# ETH-PHY.net
KiCad netlist of a schematic drawn in Altium Designer
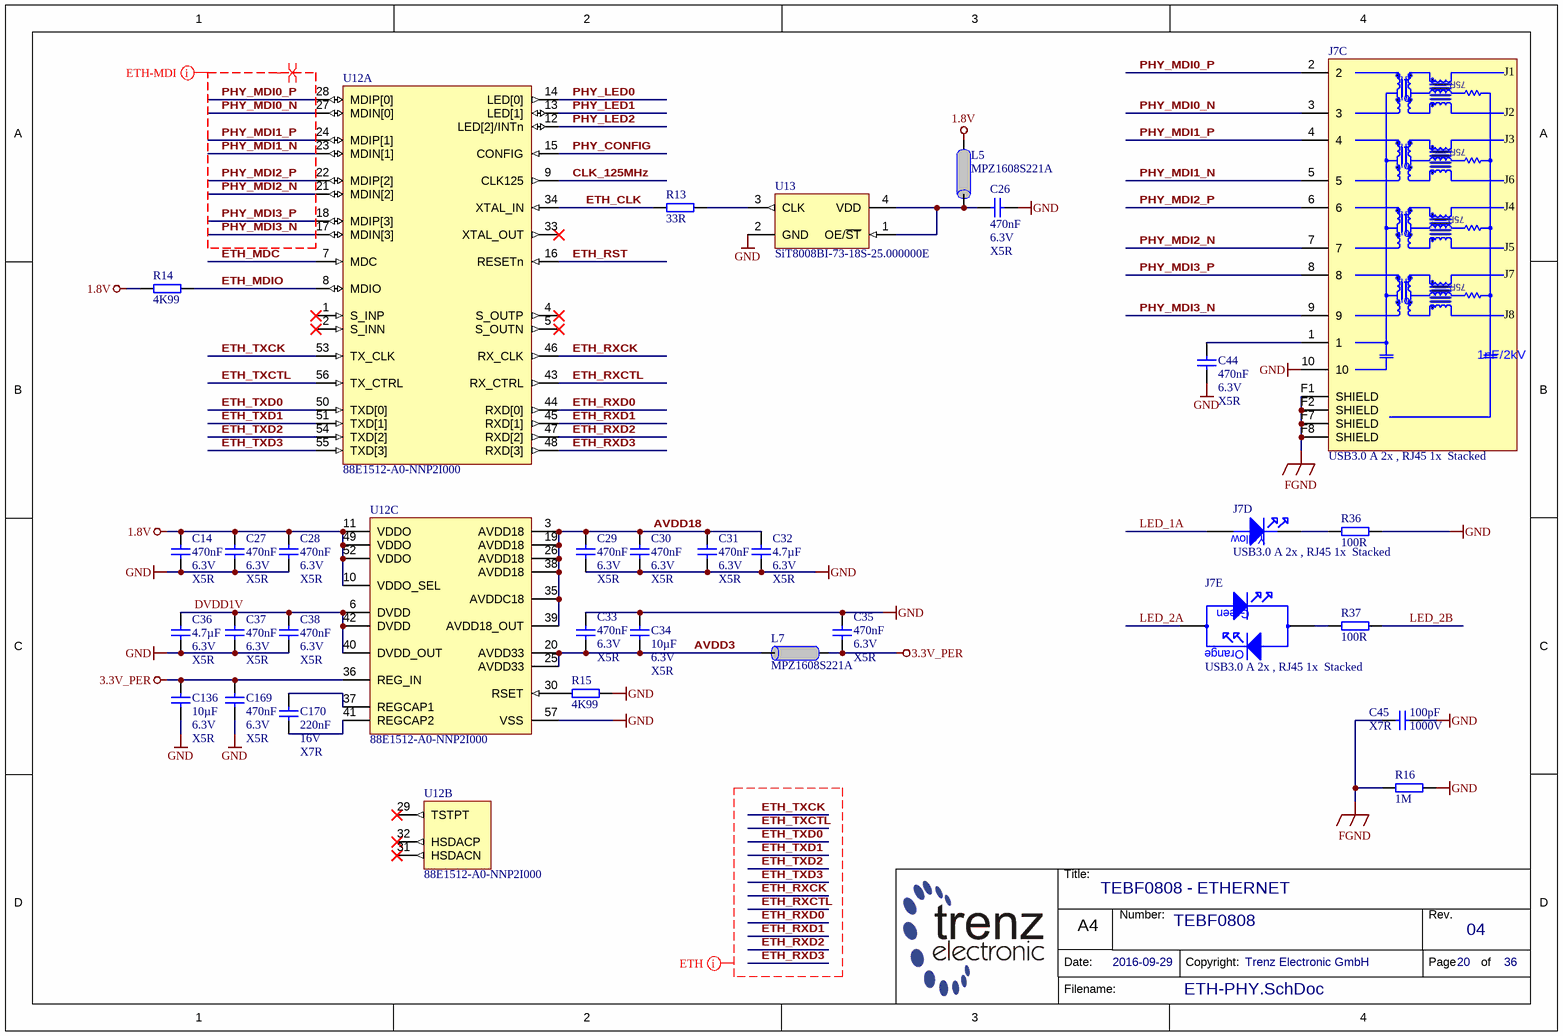
[diagram p0: ETH-PHY.SchDoc]

(export (version "E")
  (design (tool "Eeschema 10.0.6"))
  (components
    (comp (ref "C14")
      (value "470nF")
      (footprint "CAPC1005X55N")
      (description "KON 470nF 6,3V X5R SMD")
      (fields (field (name "VOLTAGE") "6.3V") (field (name "TECHNOLOGY") "X5R"))
      (libsource (lib "TE") (part "CAP-NP"))
    )
    (comp (ref "C26")
      (value "470nF")
      (footprint "CAPC1005X55N")
      (description "KON 470nF 6,3V X5R SMD")
      (fields (field (name "VOLTAGE") "6.3V") (field (name "TECHNOLOGY") "X5R"))
      (libsource (lib "TE") (part "CAP-NP"))
    )
    (comp (ref "C27")
      (value "470nF")
      (footprint "CAPC1005X55N")
      (description "KON 470nF 6,3V X5R SMD")
      (fields (field (name "VOLTAGE") "6.3V") (field (name "TECHNOLOGY") "X5R"))
      (libsource (lib "TE") (part "CAP-NP"))
    )
    (comp (ref "C28")
      (value "470nF")
      (footprint "CAPC1005X55N")
      (description "KON 470nF 6,3V X5R SMD")
      (fields (field (name "VOLTAGE") "6.3V") (field (name "TECHNOLOGY") "X5R"))
      (libsource (lib "TE") (part "CAP-NP"))
    )
    (comp (ref "C29")
      (value "470nF")
      (footprint "CAPC1005X55N")
      (description "KON 470nF 6,3V X5R SMD")
      (fields (field (name "VOLTAGE") "6.3V") (field (name "TECHNOLOGY") "X5R"))
      (libsource (lib "TE") (part "CAP-NP"))
    )
    (comp (ref "C30")
      (value "470nF")
      (footprint "CAPC1005X55N")
      (description "KON 470nF 6,3V X5R SMD")
      (fields (field (name "VOLTAGE") "6.3V") (field (name "TECHNOLOGY") "X5R"))
      (libsource (lib "TE") (part "CAP-NP"))
    )
    (comp (ref "C31")
      (value "470nF")
      (footprint "CAPC1005X55N")
      (description "KON 470nF 6,3V X5R SMD")
      (fields (field (name "VOLTAGE") "6.3V") (field (name "TECHNOLOGY") "X5R"))
      (libsource (lib "TE") (part "CAP-NP"))
    )
    (comp (ref "C32")
      (value "4.7µF")
      (footprint "CAPC1005X60N")
      (description "KON 4.7µF 6.3V X5R SMD 20%")
      (fields
        (field (name "VOLTAGE") "6.3V")
        (field (name "TECHNOLOGY") "X5R")
        (field (name "TOLERANCE") "20%")
      )
      (libsource (lib "TE") (part "CAP-NP"))
    )
    (comp (ref "C33")
      (value "470nF")
      (footprint "CAPC1005X55N")
      (description "KON 470nF 6,3V X5R SMD")
      (fields (field (name "VOLTAGE") "6.3V") (field (name "TECHNOLOGY") "X5R"))
      (libsource (lib "TE") (part "CAP-NP"))
    )
    (comp (ref "C34")
      (value "10µF")
      (footprint "CAPC1608X90N")
      (description "KON 10µF 6,3V X5R SMD")
      (fields (field (name "VOLTAGE") "6.3V") (field (name "TECHNOLOGY") "X5R"))
      (libsource (lib "TE") (part "CAP-NP"))
    )
    (comp (ref "C35")
      (value "470nF")
      (footprint "CAPC1005X55N")
      (description "KON 470nF 6,3V X5R SMD")
      (fields (field (name "VOLTAGE") "6.3V") (field (name "TECHNOLOGY") "X5R"))
      (libsource (lib "TE") (part "CAP-NP"))
    )
    (comp (ref "C36")
      (value "4.7µF")
      (footprint "CAPC1005X60N")
      (description "KON 4.7µF 6.3V X5R SMD 20%")
      (fields
        (field (name "VOLTAGE") "6.3V")
        (field (name "TECHNOLOGY") "X5R")
        (field (name "TOLERANCE") "20%")
      )
      (libsource (lib "TE") (part "CAP-NP"))
    )
    (comp (ref "C37")
      (value "470nF")
      (footprint "CAPC1005X55N")
      (description "KON 470nF 6,3V X5R SMD")
      (fields (field (name "VOLTAGE") "6.3V") (field (name "TECHNOLOGY") "X5R"))
      (libsource (lib "TE") (part "CAP-NP"))
    )
    (comp (ref "C38")
      (value "470nF")
      (footprint "CAPC1005X55N")
      (description "KON 470nF 6,3V X5R SMD")
      (fields (field (name "VOLTAGE") "6.3V") (field (name "TECHNOLOGY") "X5R"))
      (libsource (lib "TE") (part "CAP-NP"))
    )
    (comp (ref "C44")
      (value "470nF")
      (footprint "CAPC1005X55N")
      (description "KON 470nF 6,3V X5R SMD")
      (fields (field (name "VOLTAGE") "6.3V") (field (name "TECHNOLOGY") "X5R"))
      (libsource (lib "TE") (part "CAP-NP"))
    )
    (comp (ref "C45")
      (value "100pF")
      (footprint "CAPC3216X180N")
      (description "KON 100pF 1000V X7R 10%")
      (fields
        (field (name "VOLTAGE") "X7R")
        (field (name "TECHNOLOGY") "1000V")
        (field (name "TOLERANCE") "10%")
      )
      (libsource (lib "TE") (part "CAP-NP"))
    )
    (comp (ref "C136")
      (value "10µF")
      (footprint "CAPC1608X90N")
      (description "KON 10µF 6,3V X5R SMD")
      (fields (field (name "VOLTAGE") "6.3V") (field (name "TECHNOLOGY") "X5R"))
      (libsource (lib "TE") (part "CAP-NP"))
    )
    (comp (ref "C169")
      (value "470nF")
      (footprint "CAPC1005X55N")
      (description "KON 470nF 6,3V X5R SMD")
      (fields (field (name "VOLTAGE") "6.3V") (field (name "TECHNOLOGY") "X5R"))
      (libsource (lib "TE") (part "CAP-NP"))
    )
    (comp (ref "C170")
      (value "220nF")
      (footprint "CAPC1005X55N")
      (description "KON 220nF 16V X7R SMD")
      (fields (field (name "VOLTAGE") "16V") (field (name "TECHNOLOGY") "X7R"))
      (libsource (lib "TE") (part "CAP-NP"))
    )
    (comp (ref "J7")
      (value "USB3.0 A 2x , RJ45 1x  Stacked")
      (footprint "7497110616")
      (libsource (lib "") (part "7497110616_1"))
    )
    (comp (ref "L5")
      (value "MPZ1608S221A")
      (footprint "INDC1608X95N")
      (description "Ferritdurchführung MPZ1608S221A")
      (libsource (lib "TE") (part "Ferritperle"))
    )
    (comp (ref "L7")
      (value "MPZ1608S221A")
      (footprint "INDC1608X95N")
      (description "Ferritdurchführung MPZ1608S221A")
      (libsource (lib "") (part "Ferritperle_1"))
    )
    (comp (ref "R13")
      (value "33R")
      (footprint "RESC1005X40N")
      (description "WID SMD 33R 1% 0,063W")
      (fields (field (name "TOLERANCE") "1%"))
      (libsource (lib "TE") (part "RES"))
    )
    (comp (ref "R14")
      (value "4K99")
      (footprint "RESC1005X40N")
      (description "WID SMD 4K99 1% 0,063W")
      (fields (field (name "TOLERANCE") "1%"))
      (libsource (lib "TE") (part "RES"))
    )
    (comp (ref "R15")
      (value "4K99")
      (footprint "RESC1005X40N")
      (description "WID SMD 4K99 1% 0,063W")
      (fields (field (name "TOLERANCE") "1%"))
      (libsource (lib "TE") (part "RES"))
    )
    (comp (ref "R16")
      (value "1M")
      (footprint "RESC3216X65N")
      (description "WID SMD 1M 5% 0,25W")
      (fields (field (name "TOLERANCE") "5%"))
      (libsource (lib "TE") (part "RES"))
    )
    (comp (ref "R36")
      (value "100R")
      (footprint "RESC1005X40N")
      (description "WID SMD 100R 1% 0,063W")
      (fields (field (name "TOLERANCE") "1%"))
      (libsource (lib "TE") (part "RES"))
    )
    (comp (ref "R37")
      (value "100R")
      (footprint "RESC1005X40N")
      (description "WID SMD 100R 1% 0,063W")
      (fields (field (name "TOLERANCE") "1%"))
      (libsource (lib "TE") (part "RES"))
    )
    (comp (ref "U12")
      (value "88E1512-A0-NNP2I000")
      (footprint "QFN50P800X800X100-57N")
      (libsource (lib "TE") (part "88E1512"))
    )
    (comp (ref "U13")
      (value "SiT8008BI-73-18S-25.000000E")
      (footprint "2016")
      (fields (field (name "VOLTAGE") "1.8V"))
      (libsource (lib "TE") (part "SiT8103"))
    )
  )
  (nets
    (net (code "1") (name "/AVDD3") (class "Default")
      (node (ref "C33") (pin "2") (pinfunction "2_2") (pintype "passive"))
      (node (ref "C34") (pin "2") (pinfunction "2_2") (pintype "passive"))
      (node (ref "L7") (pin "2") (pinfunction "2_2") (pintype "passive"))
      (node (ref "U12") (pin "20") (pinfunction "AVDD33_20") (pintype "power_in"))
      (node (ref "U12") (pin "25") (pinfunction "AVDD33_25") (pintype "power_in"))
    )
    (net (code "2") (name "/AVDD18") (class "Default")
      (node (ref "C29") (pin "1") (pinfunction "1_1") (pintype "passive"))
      (node (ref "C30") (pin "1") (pinfunction "1_1") (pintype "passive"))
      (node (ref "C31") (pin "1") (pinfunction "1_1") (pintype "passive"))
      (node (ref "C32") (pin "1") (pinfunction "1_1") (pintype "passive"))
      (node (ref "U12") (pin "19") (pinfunction "AVDD18_19") (pintype "power_in"))
      (node (ref "U12") (pin "26") (pinfunction "AVDD18_26") (pintype "power_in"))
      (node (ref "U12") (pin "3") (pinfunction "AVDD18_3") (pintype "power_in"))
      (node (ref "U12") (pin "35") (pinfunction "AVDDC18_35") (pintype "power_in"))
      (node (ref "U12") (pin "38") (pinfunction "AVDD18_38") (pintype "power_in"))
      (node (ref "U12") (pin "39") (pinfunction "AVDD18_OUT_39") (pintype "power_in"))
    )
    (net (code "3") (name "/CLK_125MHz") (class "Default")
      (node (ref "U12") (pin "9") (pinfunction "CLK125_9") (pintype "output"))
    )
    (net (code "4") (name "/DVDD1V") (class "Default")
      (node (ref "C36") (pin "1") (pinfunction "1_1") (pintype "passive"))
      (node (ref "C37") (pin "1") (pinfunction "1_1") (pintype "passive"))
      (node (ref "C38") (pin "1") (pinfunction "1_1") (pintype "passive"))
      (node (ref "U12") (pin "40") (pinfunction "DVDD_OUT_40") (pintype "power_in"))
      (node (ref "U12") (pin "42") (pinfunction "DVDD_42") (pintype "power_in"))
      (node (ref "U12") (pin "6") (pinfunction "DVDD_6") (pintype "power_in"))
    )
    (net (code "5") (name "/ETH_CLK") (class "Default")
      (node (ref "R13") (pin "1") (pinfunction "1_1") (pintype "passive"))
      (node (ref "U12") (pin "34") (pinfunction "XTAL_IN_34") (pintype "input"))
    )
    (net (code "6") (name "/ETH_MDC") (class "Default")
      (node (ref "U12") (pin "7") (pinfunction "MDC_7") (pintype "input"))
    )
    (net (code "7") (name "/ETH_MDIO") (class "Default")
      (node (ref "R14") (pin "2") (pinfunction "2_2") (pintype "passive"))
      (node (ref "U12") (pin "8") (pinfunction "MDIO_8") (pintype "bidirectional"))
    )
    (net (code "8") (name "/ETH_RST") (class "Default")
      (node (ref "U12") (pin "16") (pinfunction "RESETn_16") (pintype "input"))
    )
    (net (code "9") (name "/ETH_RXCK") (class "Default")
      (node (ref "U12") (pin "46") (pinfunction "RX_CLK_46") (pintype "output"))
    )
    (net (code "10") (name "/ETH_RXCTL") (class "Default")
      (node (ref "U12") (pin "43") (pinfunction "RX_CTRL_43") (pintype "output"))
    )
    (net (code "11") (name "/ETH_RXD0") (class "Default")
      (node (ref "U12") (pin "44") (pinfunction "RXD[0]_44") (pintype "output"))
    )
    (net (code "12") (name "/ETH_RXD1") (class "Default")
      (node (ref "U12") (pin "45") (pinfunction "RXD[1]_45") (pintype "output"))
    )
    (net (code "13") (name "/ETH_RXD2") (class "Default")
      (node (ref "U12") (pin "47") (pinfunction "RXD[2]_47") (pintype "output"))
    )
    (net (code "14") (name "/ETH_RXD3") (class "Default")
      (node (ref "U12") (pin "48") (pinfunction "RXD[3]_48") (pintype "output"))
    )
    (net (code "15") (name "/ETH_TXCK") (class "Default")
      (node (ref "U12") (pin "53") (pinfunction "TX_CLK_53") (pintype "input"))
    )
    (net (code "16") (name "/ETH_TXCTL") (class "Default")
      (node (ref "U12") (pin "56") (pinfunction "TX_CTRL_56") (pintype "input"))
    )
    (net (code "17") (name "/ETH_TXD0") (class "Default")
      (node (ref "U12") (pin "50") (pinfunction "TXD[0]_50") (pintype "input"))
    )
    (net (code "18") (name "/ETH_TXD1") (class "Default")
      (node (ref "U12") (pin "51") (pinfunction "TXD[1]_51") (pintype "input"))
    )
    (net (code "19") (name "/ETH_TXD2") (class "Default")
      (node (ref "U12") (pin "54") (pinfunction "TXD[2]_54") (pintype "input"))
    )
    (net (code "20") (name "/ETH_TXD3") (class "Default")
      (node (ref "U12") (pin "55") (pinfunction "TXD[3]_55") (pintype "input"))
    )
    (net (code "21") (name "/LED_1A") (class "Default")
      (node (ref "J7") (pin "12") (pinfunction "12_12") (pintype "passive"))
    )
    (net (code "22") (name "/LED_2A") (class "Default")
      (node (ref "J7") (pin "14") (pinfunction "14_14") (pintype "passive"))
    )
    (net (code "23") (name "/LED_2B") (class "Default")
      (node (ref "R37") (pin "2") (pinfunction "2_2") (pintype "passive"))
    )
    (net (code "24") (name "/PHY_CONFIG") (class "Default")
      (node (ref "U12") (pin "15") (pinfunction "CONFIG_15") (pintype "input"))
    )
    (net (code "25") (name "/PHY_LED0") (class "Default")
      (node (ref "U12") (pin "14") (pinfunction "LED[0]_14") (pintype "output"))
    )
    (net (code "26") (name "/PHY_LED1") (class "Default")
      (node (ref "U12") (pin "13") (pinfunction "LED[1]_13") (pintype "bidirectional"))
    )
    (net (code "27") (name "/PHY_LED2") (class "Default")
      (node (ref "U12") (pin "12") (pinfunction "LED[2]/INTn_12") (pintype "bidirectional"))
    )
    (net (code "28") (name "/PHY_MDI0_N") (class "Default")
      (node (ref "J7") (pin "3") (pinfunction "3_3") (pintype "passive"))
      (node (ref "U12") (pin "27") (pinfunction "MDIN[0]_27") (pintype "bidirectional"))
    )
    (net (code "29") (name "/PHY_MDI0_P") (class "Default")
      (node (ref "J7") (pin "2") (pinfunction "2_2") (pintype "passive"))
      (node (ref "U12") (pin "28") (pinfunction "MDIP[0]_28") (pintype "bidirectional"))
    )
    (net (code "30") (name "/PHY_MDI1_N") (class "Default")
      (node (ref "J7") (pin "5") (pinfunction "5_5") (pintype "passive"))
      (node (ref "U12") (pin "23") (pinfunction "MDIN[1]_23") (pintype "bidirectional"))
    )
    (net (code "31") (name "/PHY_MDI1_P") (class "Default")
      (node (ref "J7") (pin "4") (pinfunction "4_4") (pintype "passive"))
      (node (ref "U12") (pin "24") (pinfunction "MDIP[1]_24") (pintype "bidirectional"))
    )
    (net (code "32") (name "/PHY_MDI2_N") (class "Default")
      (node (ref "J7") (pin "7") (pinfunction "7_7") (pintype "passive"))
      (node (ref "U12") (pin "21") (pinfunction "MDIN[2]_21") (pintype "bidirectional"))
    )
    (net (code "33") (name "/PHY_MDI2_P") (class "Default")
      (node (ref "J7") (pin "6") (pinfunction "6_6") (pintype "passive"))
      (node (ref "U12") (pin "22") (pinfunction "MDIP[2]_22") (pintype "bidirectional"))
    )
    (net (code "34") (name "/PHY_MDI3_N") (class "Default")
      (node (ref "J7") (pin "9") (pinfunction "9_9") (pintype "passive"))
      (node (ref "U12") (pin "17") (pinfunction "MDIN[3]_17") (pintype "bidirectional"))
    )
    (net (code "35") (name "/PHY_MDI3_P") (class "Default")
      (node (ref "J7") (pin "8") (pinfunction "8_8") (pintype "passive"))
      (node (ref "U12") (pin "18") (pinfunction "MDIP[3]_18") (pintype "bidirectional"))
    )
    (net (code "36") (name "1.8V") (class "Default")
      (node (ref "C14") (pin "1") (pinfunction "1_1") (pintype "passive"))
      (node (ref "C27") (pin "1") (pinfunction "1_1") (pintype "passive"))
      (node (ref "C28") (pin "1") (pinfunction "1_1") (pintype "passive"))
      (node (ref "L5") (pin "1") (pinfunction "1_1") (pintype "passive"))
      (node (ref "R14") (pin "1") (pinfunction "1_1") (pintype "passive"))
      (node (ref "U12") (pin "10") (pinfunction "VDDO_SEL_10") (pintype "power_in"))
      (node (ref "U12") (pin "11") (pinfunction "VDDO_11") (pintype "power_in"))
      (node (ref "U12") (pin "49") (pinfunction "VDDO_49") (pintype "power_in"))
      (node (ref "U12") (pin "52") (pinfunction "VDDO_52") (pintype "power_in"))
    )
    (net (code "37") (name "3.3V_PER") (class "Default")
      (node (ref "C136") (pin "1") (pinfunction "1_1") (pintype "passive"))
      (node (ref "C169") (pin "1") (pinfunction "1_1") (pintype "passive"))
      (node (ref "C35") (pin "2") (pinfunction "2_2") (pintype "passive"))
      (node (ref "L7") (pin "1") (pinfunction "1_1") (pintype "passive"))
      (node (ref "U12") (pin "36") (pinfunction "REG_IN_36") (pintype "power_in"))
    )
    (net (code "38") (name "FGND") (class "Default")
      (node (ref "C45") (pin "1") (pinfunction "1_1") (pintype "passive"))
      (node (ref "J7") (pin "F1") (pinfunction "SHIELD_F1") (pintype "passive"))
      (node (ref "J7") (pin "F2") (pinfunction "SHIELD_F2") (pintype "passive"))
      (node (ref "J7") (pin "F7") (pinfunction "SHIELD_F7") (pintype "passive"))
      (node (ref "J7") (pin "F8") (pinfunction "SHIELD_F8") (pintype "passive"))
      (node (ref "R16") (pin "1") (pinfunction "1_1") (pintype "passive"))
    )
    (net (code "39") (name "GND") (class "Default")
      (node (ref "C136") (pin "2") (pinfunction "2_2") (pintype "passive"))
      (node (ref "C14") (pin "2") (pinfunction "2_2") (pintype "passive"))
      (node (ref "C169") (pin "2") (pinfunction "2_2") (pintype "passive"))
      (node (ref "C26") (pin "2") (pinfunction "2_2") (pintype "passive"))
      (node (ref "C27") (pin "2") (pinfunction "2_2") (pintype "passive"))
      (node (ref "C28") (pin "2") (pinfunction "2_2") (pintype "passive"))
      (node (ref "C29") (pin "2") (pinfunction "2_2") (pintype "passive"))
      (node (ref "C30") (pin "2") (pinfunction "2_2") (pintype "passive"))
      (node (ref "C31") (pin "2") (pinfunction "2_2") (pintype "passive"))
      (node (ref "C32") (pin "2") (pinfunction "2_2") (pintype "passive"))
      (node (ref "C33") (pin "1") (pinfunction "1_1") (pintype "passive"))
      (node (ref "C34") (pin "1") (pinfunction "1_1") (pintype "passive"))
      (node (ref "C35") (pin "1") (pinfunction "1_1") (pintype "passive"))
      (node (ref "C36") (pin "2") (pinfunction "2_2") (pintype "passive"))
      (node (ref "C37") (pin "2") (pinfunction "2_2") (pintype "passive"))
      (node (ref "C38") (pin "2") (pinfunction "2_2") (pintype "passive"))
      (node (ref "C44") (pin "2") (pinfunction "2_2") (pintype "passive"))
      (node (ref "C45") (pin "2") (pinfunction "2_2") (pintype "passive"))
      (node (ref "J7") (pin "10") (pinfunction "10_10") (pintype "passive"))
      (node (ref "R15") (pin "2") (pinfunction "2_2") (pintype "passive"))
      (node (ref "R16") (pin "2") (pinfunction "2_2") (pintype "passive"))
      (node (ref "R36") (pin "2") (pinfunction "2_2") (pintype "passive"))
      (node (ref "U12") (pin "57") (pinfunction "VSS_57") (pintype "power_in"))
      (node (ref "U13") (pin "2") (pinfunction "GND_2") (pintype "power_in"))
    )
    (net (code "40") (name "Net-(C44-Pad1)") (class "Default")
      (node (ref "C44") (pin "1") (pinfunction "1_1") (pintype "passive"))
      (node (ref "J7") (pin "1") (pinfunction "1_1") (pintype "passive"))
    )
    (net (code "41") (name "Net-(J7-Pad11)") (class "Default")
      (node (ref "J7") (pin "11") (pinfunction "11_11") (pintype "passive"))
      (node (ref "R36") (pin "1") (pinfunction "1_1") (pintype "passive"))
    )
    (net (code "42") (name "Net-(J7-Pad13)") (class "Default")
      (node (ref "J7") (pin "13") (pinfunction "13_13") (pintype "passive"))
      (node (ref "R37") (pin "1") (pinfunction "1_1") (pintype "passive"))
    )
    (net (code "43") (name "Net-(U12C-REGCAP1)") (class "Default")
      (node (ref "C170") (pin "1") (pinfunction "1_1") (pintype "passive"))
      (node (ref "U12") (pin "37") (pinfunction "REGCAP1_37") (pintype "passive"))
    )
    (net (code "44") (name "Net-(U12C-REGCAP2)") (class "Default")
      (node (ref "C170") (pin "2") (pinfunction "2_2") (pintype "passive"))
      (node (ref "U12") (pin "41") (pinfunction "REGCAP2_41") (pintype "passive"))
    )
    (net (code "45") (name "Net-(U12C-RSET)") (class "Default")
      (node (ref "R15") (pin "1") (pinfunction "1_1") (pintype "passive"))
      (node (ref "U12") (pin "30") (pinfunction "RSET_30") (pintype "input"))
    )
    (net (code "46") (name "Net-(U13-CLK)") (class "Default")
      (node (ref "R13") (pin "2") (pinfunction "2_2") (pintype "passive"))
      (node (ref "U13") (pin "3") (pinfunction "CLK_3") (pintype "output"))
    )
    (net (code "47") (name "Net-(U13-OE{slash}~{ST})") (class "Default")
      (node (ref "C26") (pin "1") (pinfunction "1_1") (pintype "passive"))
      (node (ref "L5") (pin "2") (pinfunction "2_2") (pintype "passive"))
      (node (ref "U13") (pin "1") (pinfunction "OE/~{ST}_1") (pintype "input"))
      (node (ref "U13") (pin "4") (pinfunction "VDD_4") (pintype "power_in"))
    )
    (net (code "48") (name "unconnected-(U12A-S_INN-Pad2)") (class "Default")
      (node (ref "U12") (pin "2") (pinfunction "S_INN_2") (pintype "input+no_connect"))
    )
    (net (code "49") (name "unconnected-(U12A-S_INP-Pad1)") (class "Default")
      (node (ref "U12") (pin "1") (pinfunction "S_INP_1") (pintype "input+no_connect"))
    )
    (net (code "50") (name "unconnected-(U12A-S_OUTN-Pad5)") (class "Default")
      (node (ref "U12") (pin "5") (pinfunction "S_OUTN_5") (pintype "output+no_connect"))
    )
    (net (code "51") (name "unconnected-(U12A-S_OUTP-Pad4)") (class "Default")
      (node (ref "U12") (pin "4") (pinfunction "S_OUTP_4") (pintype "output+no_connect"))
    )
    (net (code "52") (name "unconnected-(U12A-XTAL_OUT-Pad33)") (class "Default")
      (node (ref "U12") (pin "33") (pinfunction "XTAL_OUT_33") (pintype "output+no_connect"))
    )
    (net (code "53") (name "unconnected-(U12B-HSDACN-Pad31)") (class "Default")
      (node (ref "U12") (pin "31") (pinfunction "HSDACN_31") (pintype "output+no_connect"))
    )
    (net (code "54") (name "unconnected-(U12B-HSDACP-Pad32)") (class "Default")
      (node (ref "U12") (pin "32") (pinfunction "HSDACP_32") (pintype "output+no_connect"))
    )
    (net (code "55") (name "unconnected-(U12B-TSTPT-Pad29)") (class "Default")
      (node (ref "U12") (pin "29") (pinfunction "TSTPT_29") (pintype "output+no_connect"))
    )
  )
)
